# DCDC_Converter.net
KiCad netlist of a schematic drawn in Altium Designer
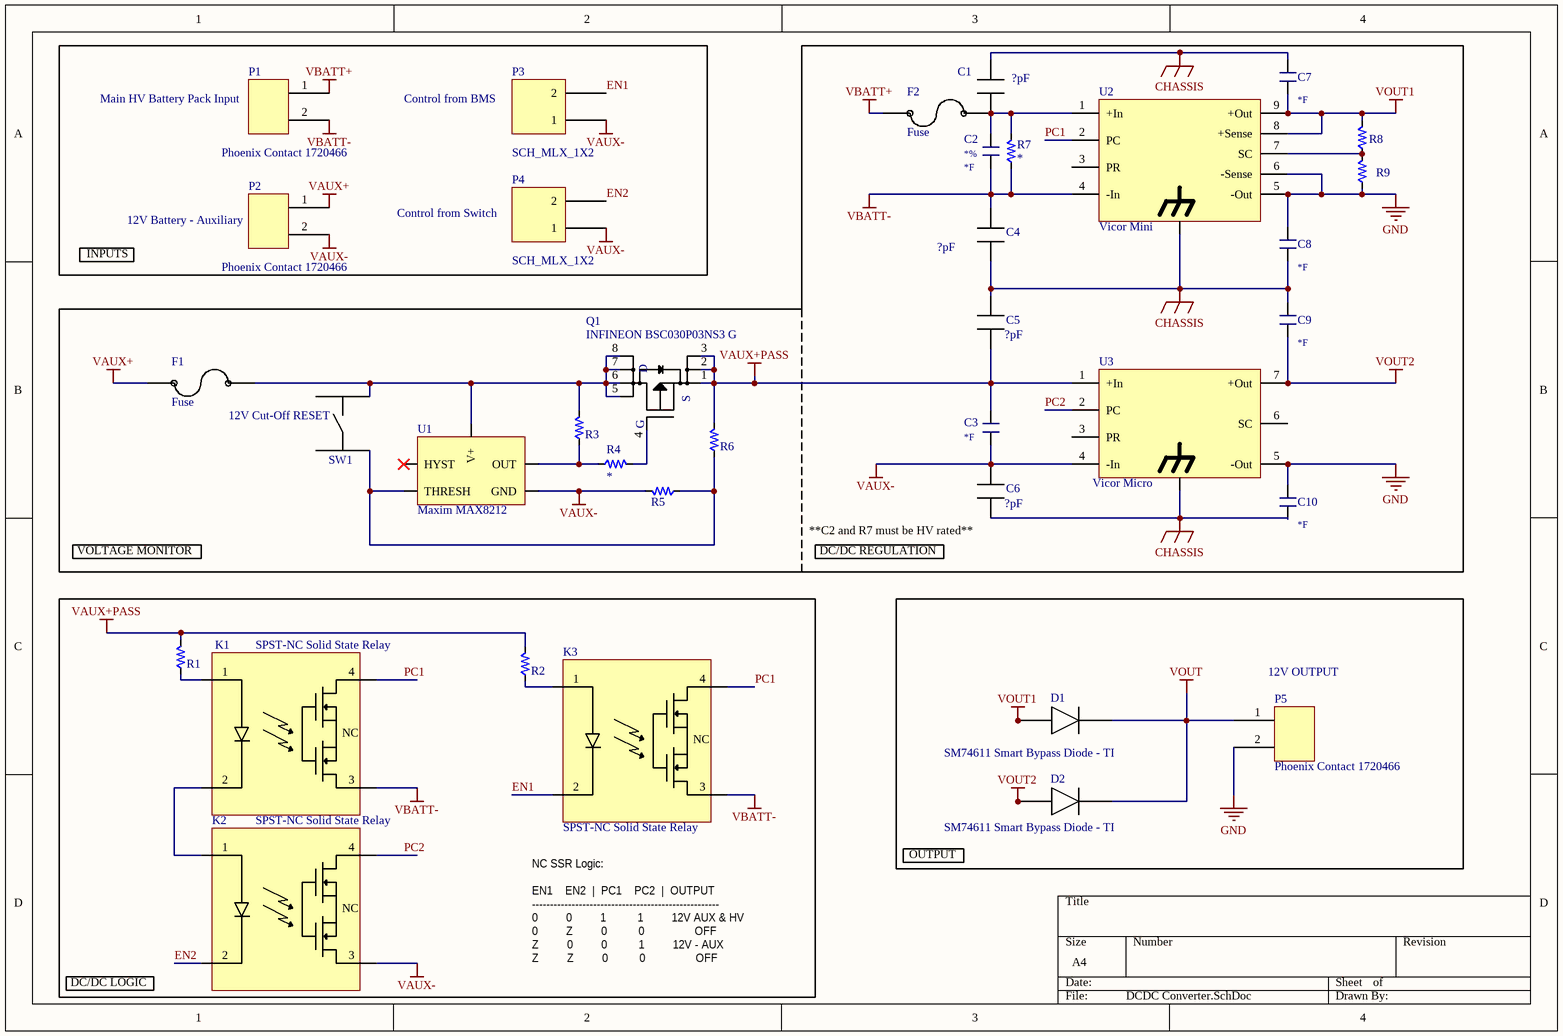
[diagram p0: DCDC Converter.SchDoc]

(export (version "E")
  (design (tool "Eeschema 10.0.6"))
  (components
    (comp (ref "C1")
      (value "X1-Y2 Capacitor")
      (footprint "Murata 2220 X1-Y2 Capacitor")
      (fields (field (name "CAPACITANCE") "?pF"))
      (libsource (lib "Murata 2220 X1-Y2 Capacitor") (part "Murata 2220 X1-Y2 Capacitor"))
    )
    (comp (ref "C2")
      (value "SCH_GENERIC_CAPACITOR_1210")
      (footprint "PCB_GENERIC_CAPACITOR_1210")
      (description "Generic SMD capacitor 1210")
      (fields (field (name "TOLERANCE") "*%") (field (name "CAPACITANCE") "*F"))
      (libsource (lib "Generic 1210 Capacitor") (part "SCH_GENERIC_CAPACITOR_1210"))
    )
    (comp (ref "C3")
      (value "SCH_GENERIC_CAPACITOR_0603")
      (footprint "PCB_GENERIC_SMD_0603")
      (description "Generic SMD capacitor 0603")
      (fields (field (name "TOLERANCE") "*%") (field (name "CAPACITANCE") "*F"))
      (libsource (lib "Generic 0603 Capacitor") (part "SCH_GENERIC_CAPACITOR_0603"))
    )
    (comp (ref "C4")
      (value "X1-Y2 Capacitor")
      (footprint "Murata 2220 X1-Y2 Capacitor")
      (fields (field (name "CAPACITANCE") "?pF"))
      (libsource (lib "Murata 2220 X1-Y2 Capacitor") (part "Murata 2220 X1-Y2 Capacitor"))
    )
    (comp (ref "C5")
      (value "X1-Y2 Capacitor")
      (footprint "Murata 2220 X1-Y2 Capacitor")
      (fields (field (name "CAPACITANCE") "?pF"))
      (libsource (lib "Murata 2220 X1-Y2 Capacitor") (part "Murata 2220 X1-Y2 Capacitor"))
    )
    (comp (ref "C6")
      (value "X1-Y2 Capacitor")
      (footprint "Murata 2220 X1-Y2 Capacitor")
      (fields (field (name "CAPACITANCE") "?pF"))
      (libsource (lib "Murata 2220 X1-Y2 Capacitor") (part "Murata 2220 X1-Y2 Capacitor"))
    )
    (comp (ref "C7")
      (value "SCH_GENERIC_CAPACITOR_0603")
      (footprint "PCB_GENERIC_SMD_0603")
      (description "Generic SMD capacitor 0603")
      (fields (field (name "TOLERANCE") "*%") (field (name "CAPACITANCE") "*F"))
      (libsource (lib "Generic 0603 Capacitor") (part "SCH_GENERIC_CAPACITOR_0603"))
    )
    (comp (ref "C8")
      (value "SCH_GENERIC_CAPACITOR_0603")
      (footprint "PCB_GENERIC_SMD_0603")
      (description "Generic SMD capacitor 0603")
      (fields (field (name "TOLERANCE") "*%") (field (name "CAPACITANCE") "*F"))
      (libsource (lib "Generic 0603 Capacitor") (part "SCH_GENERIC_CAPACITOR_0603"))
    )
    (comp (ref "C9")
      (value "SCH_GENERIC_CAPACITOR_0603")
      (footprint "PCB_GENERIC_SMD_0603")
      (description "Generic SMD capacitor 0603")
      (fields (field (name "TOLERANCE") "*%") (field (name "CAPACITANCE") "*F"))
      (libsource (lib "Generic 0603 Capacitor") (part "SCH_GENERIC_CAPACITOR_0603"))
    )
    (comp (ref "C10")
      (value "SCH_GENERIC_CAPACITOR_0603")
      (footprint "PCB_GENERIC_SMD_0603")
      (description "Generic SMD capacitor 0603")
      (fields (field (name "TOLERANCE") "*%") (field (name "CAPACITANCE") "*F"))
      (libsource (lib "Generic 0603 Capacitor") (part "SCH_GENERIC_CAPACITOR_0603"))
    )
    (comp (ref "D1")
      (value "SM74611 Smart Bypass Diode - TI")
      (footprint "SM74611 Smart Bypass Diode - TI")
      (libsource (lib "SM74611 Smart Bypass Diode - TI") (part "SM74611 Smart Bypass Diode - TI"))
    )
    (comp (ref "D2")
      (value "SM74611 Smart Bypass Diode - TI")
      (footprint "SM74611 Smart Bypass Diode - TI")
      (libsource (lib "SM74611 Smart Bypass Diode - TI") (part "SM74611 Smart Bypass Diode - TI"))
    )
    (comp (ref "F1")
      (value "Fuse")
      (footprint "Schurter 5x20mm Fuse Holder")
      (libsource (lib "Fuse Holder") (part "Fuse"))
    )
    (comp (ref "F2")
      (value "Fuse")
      (footprint "Schurter 5x20mm Fuse Holder")
      (libsource (lib "Fuse Holder") (part "Fuse"))
    )
    (comp (ref "K1")
      (value "SPST-NC Solid State Relay")
      (footprint "SPST-NC Solid State Relay - IXYS")
      (libsource (lib "SPST-NC Solid State Relay") (part "SPST-NC Solid State Relay"))
    )
    (comp (ref "K2")
      (value "SPST-NC Solid State Relay")
      (footprint "SPST-NC Solid State Relay - IXYS")
      (libsource (lib "SPST-NC Solid State Relay") (part "SPST-NC Solid State Relay"))
    )
    (comp (ref "K3")
      (value "SPST-NC Solid State Relay")
      (footprint "SPST-NC Solid State Relay - IXYS")
      (libsource (lib "SPST-NC Solid State Relay") (part "SPST-NC Solid State Relay"))
    )
    (comp (ref "P1")
      (value "Phoenix Contact 1720466")
      (footprint "Phoenix Contact 1720466")
      (libsource (lib "Phoenix Contact 1720466") (part "Phoenix Contact 1720466"))
    )
    (comp (ref "P2")
      (value "Phoenix Contact 1720466")
      (footprint "Phoenix Contact 1720466")
      (libsource (lib "Phoenix Contact 1720466") (part "Phoenix Contact 1720466"))
    )
    (comp (ref "P3")
      (value "SCH_MLX_1X2")
      (footprint "PCB_MLX_MICROFIT_1X2")
      (libsource (lib "Molex Microfit 3.0 1x2") (part "SCH_MLX_1X2"))
    )
    (comp (ref "P4")
      (value "SCH_MLX_1X2")
      (footprint "PCB_MLX_MICROFIT_1X2")
      (libsource (lib "Molex Microfit 3.0 1x2") (part "SCH_MLX_1X2"))
    )
    (comp (ref "P5")
      (value "Phoenix Contact 1720466")
      (footprint "Phoenix Contact 1720466")
      (libsource (lib "") (part "Phoenix Contact 1720466_1"))
    )
    (comp (ref "Q1")
      (value "INFINEON BSC030P03NS3 G")
      (footprint "BSC030P03NS3 G")
      (description "P-Channel 30V 25.4A (Ta), 100A (Tc) 2.5W (Ta), 125W (Tc) Surface Mount PG-TDSON-8")
      (fields (field (name "DIGIKEY PART NO.") "BSC030P03NS3 GCT-ND"))
      (libsource (lib "Infineon BSC030P03NS3 G - 8-PowerTDFN - PMOS") (part "BSC030P03NS3 G"))
    )
    (comp (ref "R1")
      (value "SCH_GENERIC_RESISTOR_0603")
      (footprint "PCB_GENERIC_SMD_0603")
      (description "Generic SMD resistor 0603")
      (libsource (lib "Generic 0603 Resistor") (part "SCH_GENERIC_RESISTOR_0603"))
    )
    (comp (ref "R2")
      (value "SCH_GENERIC_RESISTOR_0603")
      (footprint "PCB_GENERIC_SMD_0603")
      (description "Generic SMD resistor 0603")
      (libsource (lib "Generic 0603 Resistor") (part "SCH_GENERIC_RESISTOR_0603"))
    )
    (comp (ref "R3")
      (value "SCH_GENERIC_RESISTOR_0603")
      (footprint "PCB_GENERIC_SMD_0603")
      (description "Generic SMD resistor 0603")
      (libsource (lib "Generic 0603 Resistor") (part "SCH_GENERIC_RESISTOR_0603"))
    )
    (comp (ref "R4")
      (value "SCH_GENERIC_RESISTOR_0603")
      (footprint "PCB_GENERIC_SMD_0603")
      (description "Generic SMD resistor 0603")
      (fields (field (name "RESISTANCE") "*"))
      (libsource (lib "Generic 0603 Resistor") (part "SCH_GENERIC_RESISTOR_0603"))
    )
    (comp (ref "R5")
      (value "SCH_GENERIC_RESISTOR_0603")
      (footprint "PCB_GENERIC_SMD_0603")
      (description "Generic SMD resistor 0603")
      (libsource (lib "Generic 0603 Resistor") (part "SCH_GENERIC_RESISTOR_0603"))
    )
    (comp (ref "R6")
      (value "SCH_GENERIC_RESISTOR_0603")
      (footprint "PCB_GENERIC_SMD_0603")
      (description "Generic SMD resistor 0603")
      (libsource (lib "Generic 0603 Resistor") (part "SCH_GENERIC_RESISTOR_0603"))
    )
    (comp (ref "R7")
      (value "SCH_GENERIC_RESISTOR_1206")
      (footprint "PCB_GENERIC_SMD_1206")
      (description "Generic SMD resistor 1206")
      (fields (field (name "RESISTANCE") "*"))
      (libsource (lib "Generic 1206 Resistor") (part "SCH_GENERIC_RESISTOR_1206"))
    )
    (comp (ref "R8")
      (value "SCH_GENERIC_RESISTOR_0603")
      (footprint "PCB_GENERIC_SMD_0603")
      (description "Generic SMD resistor 0603")
      (libsource (lib "Generic 0603 Resistor") (part "SCH_GENERIC_RESISTOR_0603"))
    )
    (comp (ref "R9")
      (value "SCH_GENERIC_RESISTOR_0603")
      (footprint "PCB_GENERIC_SMD_0603")
      (description "Generic SMD resistor 0603")
      (libsource (lib "Generic 0603 Resistor") (part "SCH_GENERIC_RESISTOR_0603"))
    )
    (comp (ref "SW1")
      (value "Tactile Switch")
      (footprint "C&K 4 pin Tactile Switch")
      (libsource (lib "C&K 4 Pin Tactile Switch") (part "C&K Tactile Switch"))
    )
    (comp (ref "U1")
      (value "Maxim MAX8212")
      (footprint "Maxim MAX8212")
      (libsource (lib "Maxim MAX8212") (part "Maxim MAX8212"))
    )
    (comp (ref "U2")
      (value "Vicor Mini")
      (footprint "Vicor_Mini")
      (libsource (lib "Vicor_MaxiMiniMicro") (part "Vicor Mini"))
    )
    (comp (ref "U3")
      (value "Vicor Micro")
      (footprint "Vicor_Micro")
      (libsource (lib "Vicor_MaxiMiniMicro") (part "Vicor Micro"))
    )
  )
  (nets
    (net (code "1") (name "/EN1") (class "Default")
      (node (ref "K3") (pin "2") (pinfunction "Control_-_2") (pintype "passive"))
      (node (ref "P3") (pin "2") (pinfunction "2_2") (pintype "passive"))
    )
    (net (code "2") (name "/EN2") (class "Default")
      (node (ref "K2") (pin "2") (pinfunction "Control_-_2") (pintype "passive"))
      (node (ref "P4") (pin "2") (pinfunction "2_2") (pintype "passive"))
    )
    (net (code "3") (name "/PC1") (class "Default")
      (node (ref "K1") (pin "4") (pinfunction "Load_4") (pintype "passive"))
      (node (ref "K3") (pin "4") (pinfunction "Load_4") (pintype "passive"))
      (node (ref "U2") (pin "2") (pinfunction "PC_2") (pintype "passive"))
    )
    (net (code "4") (name "/PC2") (class "Default")
      (node (ref "K2") (pin "4") (pinfunction "Load_4") (pintype "passive"))
      (node (ref "U3") (pin "2") (pinfunction "PC_2") (pintype "passive"))
    )
    (net (code "5") (name "CHASSIS") (class "Default")
      (node (ref "C1") (pin "2") (pintype "passive"))
      (node (ref "C10") (pin "1") (pinfunction "1_1") (pintype "passive"))
      (node (ref "C4") (pin "1") (pintype "passive"))
      (node (ref "C5") (pin "2") (pintype "passive"))
      (node (ref "C6") (pin "1") (pintype "passive"))
      (node (ref "C7") (pin "2") (pinfunction "2_2") (pintype "passive"))
      (node (ref "C8") (pin "1") (pinfunction "1_1") (pintype "passive"))
      (node (ref "C9") (pin "2") (pinfunction "2_2") (pintype "passive"))
      (node (ref "U2") (pin "0") (pinfunction "CHASSIS_GROUND_0") (pintype "passive"))
      (node (ref "U3") (pin "0") (pinfunction "CHASSIS_GROUND_0") (pintype "passive"))
    )
    (net (code "6") (name "GND") (class "Default")
      (node (ref "C10") (pin "2") (pinfunction "2_2") (pintype "passive"))
      (node (ref "C8") (pin "2") (pinfunction "2_2") (pintype "passive"))
      (node (ref "P5") (pin "2") (pinfunction "2_2") (pintype "passive"))
      (node (ref "R9") (pin "1") (pinfunction "1_1") (pintype "passive"))
      (node (ref "U2") (pin "5") (pinfunction "-Out_5") (pintype "passive"))
      (node (ref "U2") (pin "6") (pinfunction "-Sense_6") (pintype "passive"))
      (node (ref "U3") (pin "5") (pinfunction "-Out_5") (pintype "passive"))
    )
    (net (code "7") (name "Net-(K1-Control_+)") (class "Default")
      (node (ref "K1") (pin "1") (pinfunction "Control_+_1") (pintype "passive"))
      (node (ref "R1") (pin "1") (pinfunction "1_1") (pintype "passive"))
    )
    (net (code "8") (name "Net-(K1-Control_-)") (class "Default")
      (node (ref "K1") (pin "2") (pinfunction "Control_-_2") (pintype "passive"))
      (node (ref "K2") (pin "1") (pinfunction "Control_+_1") (pintype "passive"))
    )
    (net (code "9") (name "Net-(K3-Control_+)") (class "Default")
      (node (ref "K3") (pin "1") (pinfunction "Control_+_1") (pintype "passive"))
      (node (ref "R2") (pin "1") (pinfunction "1_1") (pintype "passive"))
    )
    (net (code "10") (name "Net-(Q1-G)") (class "Default")
      (node (ref "Q1") (pin "4") (pinfunction "G_4") (pintype "passive"))
      (node (ref "R4") (pin "2") (pinfunction "2_2") (pintype "passive"))
    )
    (net (code "11") (name "Net-(U1-OUT)") (class "Default")
      (node (ref "R3") (pin "1") (pinfunction "1_1") (pintype "passive"))
      (node (ref "R4") (pin "1") (pinfunction "1_1") (pintype "passive"))
      (node (ref "U1") (pin "4") (pinfunction "OUT_4") (pintype "passive"))
    )
    (net (code "12") (name "Net-(U1-THRESH)") (class "Default")
      (node (ref "R5") (pin "1") (pinfunction "1_1") (pintype "passive"))
      (node (ref "R6") (pin "1") (pinfunction "1_1") (pintype "passive"))
      (node (ref "SW1") (pin "1") (pintype "passive"))
      (node (ref "U1") (pin "3") (pinfunction "THRESH_3") (pintype "passive"))
    )
    (net (code "13") (name "Net-(U1-V+)") (class "Default")
      (node (ref "F1") (pin "2") (pintype "passive"))
      (node (ref "Q1") (pin "5") (pinfunction "D_5") (pintype "passive"))
      (node (ref "Q1") (pin "6") (pinfunction "D_6") (pintype "passive"))
      (node (ref "Q1") (pin "7") (pinfunction "D_7") (pintype "passive"))
      (node (ref "Q1") (pin "8") (pinfunction "D_8") (pintype "passive"))
      (node (ref "R3") (pin "2") (pinfunction "2_2") (pintype "passive"))
      (node (ref "SW1") (pin "3") (pinfunction "3_3") (pintype "passive"))
      (node (ref "U1") (pin "8") (pinfunction "V+_8") (pintype "passive"))
    )
    (net (code "14") (name "Net-(U2-+In)") (class "Default")
      (node (ref "C1") (pin "1") (pintype "passive"))
      (node (ref "C2") (pin "2") (pinfunction "2_2") (pintype "passive"))
      (node (ref "F2") (pin "2") (pintype "passive"))
      (node (ref "R7") (pin "2") (pinfunction "2_2") (pintype "passive"))
      (node (ref "U2") (pin "1") (pinfunction "+In_1") (pintype "passive"))
    )
    (net (code "15") (name "Net-(U2-SC)") (class "Default")
      (node (ref "R8") (pin "1") (pinfunction "1_1") (pintype "passive"))
      (node (ref "R9") (pin "2") (pinfunction "2_2") (pintype "passive"))
      (node (ref "U2") (pin "7") (pinfunction "SC_7") (pintype "passive"))
    )
    (net (code "16") (name "VAUX+") (class "Default")
      (node (ref "F1") (pin "1") (pintype "passive"))
      (node (ref "P2") (pin "1") (pinfunction "1_1") (pintype "passive"))
    )
    (net (code "17") (name "VAUX+PASS") (class "Default")
      (node (ref "C3") (pin "2") (pinfunction "2_2") (pintype "passive"))
      (node (ref "C5") (pin "1") (pintype "passive"))
      (node (ref "Q1") (pin "1") (pinfunction "S_1") (pintype "passive"))
      (node (ref "Q1") (pin "2") (pinfunction "S_2") (pintype "passive"))
      (node (ref "Q1") (pin "3") (pinfunction "S_3") (pintype "passive"))
      (node (ref "R1") (pin "2") (pinfunction "2_2") (pintype "passive"))
      (node (ref "R2") (pin "2") (pinfunction "2_2") (pintype "passive"))
      (node (ref "R6") (pin "2") (pinfunction "2_2") (pintype "passive"))
      (node (ref "U3") (pin "1") (pinfunction "+In_1") (pintype "passive"))
    )
    (net (code "18") (name "VAUX-") (class "Default")
      (node (ref "C3") (pin "1") (pinfunction "1_1") (pintype "passive"))
      (node (ref "C6") (pin "2") (pintype "passive"))
      (node (ref "K2") (pin "3") (pinfunction "Load_3") (pintype "passive"))
      (node (ref "P2") (pin "2") (pinfunction "2_2") (pintype "passive"))
      (node (ref "P3") (pin "1") (pinfunction "1_1") (pintype "passive"))
      (node (ref "P4") (pin "1") (pinfunction "1_1") (pintype "passive"))
      (node (ref "R5") (pin "2") (pinfunction "2_2") (pintype "passive"))
      (node (ref "U1") (pin "5") (pinfunction "GND_5") (pintype "passive"))
      (node (ref "U3") (pin "4") (pinfunction "-In_4") (pintype "passive"))
    )
    (net (code "19") (name "VBATT+") (class "Default")
      (node (ref "F2") (pin "1") (pintype "passive"))
      (node (ref "P1") (pin "1") (pinfunction "1_1") (pintype "passive"))
    )
    (net (code "20") (name "VBATT-") (class "Default")
      (node (ref "C2") (pin "1") (pinfunction "1_1") (pintype "passive"))
      (node (ref "C4") (pin "2") (pintype "passive"))
      (node (ref "K1") (pin "3") (pinfunction "Load_3") (pintype "passive"))
      (node (ref "K3") (pin "3") (pinfunction "Load_3") (pintype "passive"))
      (node (ref "P1") (pin "2") (pinfunction "2_2") (pintype "passive"))
      (node (ref "R7") (pin "1") (pinfunction "1_1") (pintype "passive"))
      (node (ref "U2") (pin "4") (pinfunction "-In_4") (pintype "passive"))
    )
    (net (code "21") (name "VOUT") (class "Default")
      (node (ref "D1") (pin "4") (pintype "passive"))
      (node (ref "D2") (pin "4") (pintype "passive"))
      (node (ref "P5") (pin "1") (pinfunction "1_1") (pintype "passive"))
    )
    (net (code "22") (name "VOUT1") (class "Default")
      (node (ref "C7") (pin "1") (pinfunction "1_1") (pintype "passive"))
      (node (ref "D1") (pin "1") (pintype "passive"))
      (node (ref "D1") (pin "3") (pintype "passive"))
      (node (ref "R8") (pin "2") (pinfunction "2_2") (pintype "passive"))
      (node (ref "U2") (pin "8") (pinfunction "+Sense_8") (pintype "passive"))
      (node (ref "U2") (pin "9") (pinfunction "+Out_9") (pintype "passive"))
    )
    (net (code "23") (name "VOUT2") (class "Default")
      (node (ref "C9") (pin "1") (pinfunction "1_1") (pintype "passive"))
      (node (ref "D2") (pin "1") (pintype "passive"))
      (node (ref "D2") (pin "3") (pintype "passive"))
      (node (ref "U3") (pin "7") (pinfunction "+Out_7") (pintype "passive"))
    )
    (net (code "24") (name "unconnected-(SW1-Pad2)") (class "Default")
      (node (ref "SW1") (pin "2") (pinfunction "2_2") (pintype "passive"))
    )
    (net (code "25") (name "unconnected-(SW1-Pad4)") (class "Default")
      (node (ref "SW1") (pin "4") (pinfunction "4_4") (pintype "passive"))
    )
    (net (code "26") (name "unconnected-(U1-HYST-Pad2)") (class "Default")
      (node (ref "U1") (pin "2") (pinfunction "HYST_2") (pintype "passive+no_connect"))
    )
    (net (code "27") (name "unconnected-(U2-PR-Pad3)") (class "Default")
      (node (ref "U2") (pin "3") (pinfunction "PR_3") (pintype "passive"))
    )
    (net (code "28") (name "unconnected-(U3-PR-Pad3)") (class "Default")
      (node (ref "U3") (pin "3") (pinfunction "PR_3") (pintype "passive"))
    )
    (net (code "29") (name "unconnected-(U3-SC-Pad6)") (class "Default")
      (node (ref "U3") (pin "6") (pinfunction "SC_6") (pintype "passive"))
    )
  )
)
